# Capstone.net
KiCad netlist of a schematic drawn in Altium Designer
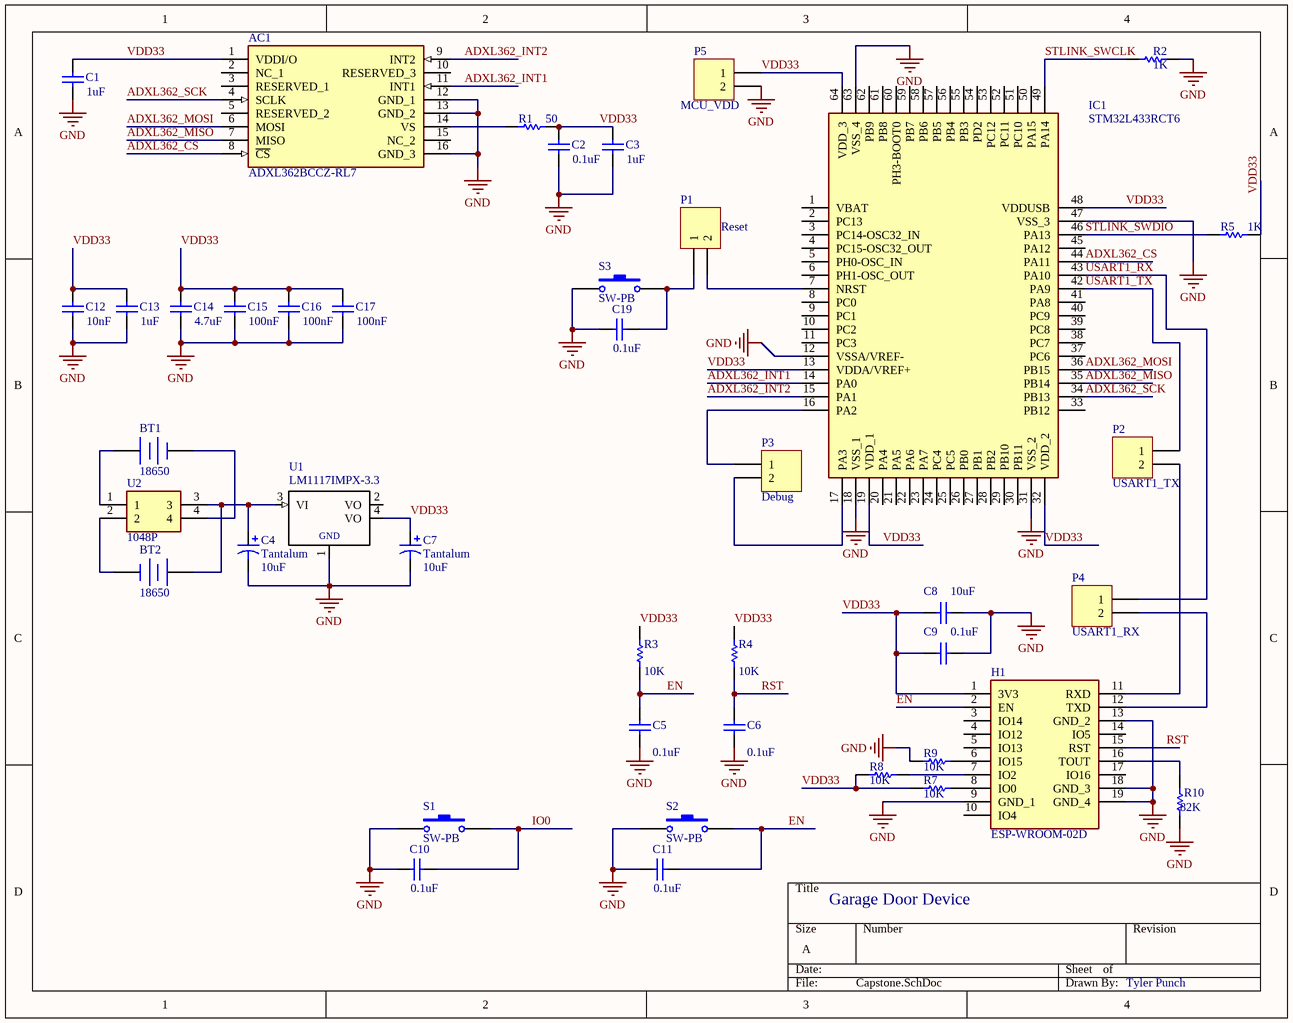
[diagram p0: Capstone.SchDoc]

(export (version "E")
  (design (tool "Eeschema 10.0.6"))
  (components
    (comp (ref "AC1")
      (value "ADXL362BCCZ-RL7")
      (footprint "SamacSys:CC-16-4")
      (description "Accelerometer")
      (fields (field (name "MOUSER PART NUMBER") "584-ADXL362BCCZ-R7"))
      (libsource (lib "*") (part "ADXL362BCCZ-RL7"))
    )
    (comp (ref "BT1")
      (value "18650")
      (footprint "BAT-2")
      (description "Multicell Battery")
      (fields (field (name "PUBLISHER") "Altium Limited"))
      (libsource (lib "Miscellaneous Devices") (part "Battery"))
    )
    (comp (ref "BT2")
      (value "18650")
      (footprint "BAT-2")
      (description "Multicell Battery")
      (fields (field (name "PUBLISHER") "Altium Limited"))
      (libsource (lib "Miscellaneous Devices") (part "Battery"))
    )
    (comp (ref "C1")
      (value "1uF")
      (footprint "*CAPC2012X88N")
      (description "Capacitor")
      (fields (field (name "Comment") "Cap") (field (name "PUBLISHER") "Altium Limited"))
      (libsource (lib "C0805C106K8PACTU") (part "Cap"))
    )
    (comp (ref "C2")
      (value "0.1uF")
      (footprint "*CAPC2012X88N")
      (description "Capacitor")
      (fields (field (name "Comment") "Cap") (field (name "PUBLISHER") "Altium Limited"))
      (libsource (lib "Miscellaneous Devices") (part "Cap"))
    )
    (comp (ref "C3")
      (value "1uF")
      (footprint "*CAPC2012X88N")
      (description "Capacitor")
      (fields (field (name "Comment") "Cap") (field (name "PUBLISHER") "Altium Limited"))
      (libsource (lib "Miscellaneous Devices") (part "Cap"))
    )
    (comp (ref "C4")
      (value "Tantalum")
      (footprint "RB7.6-15")
      (description "Polarized Capacitor (Radial)")
      (fields (field (name "ALTIUM_VALUE") "10uF") (field (name "PUBLISHER") "Altium Limited"))
      (libsource (lib "Miscellaneous Devices") (part "Cap Pol1"))
    )
    (comp (ref "C5")
      (value "0.1uF")
      (footprint "*CAPC2012X88N")
      (description "Capacitor")
      (fields (field (name "Comment") "Cap") (field (name "PUBLISHER") "Altium Limited"))
      (libsource (lib "Miscellaneous Devices") (part "Cap"))
    )
    (comp (ref "C6")
      (value "0.1uF")
      (footprint "*CAPC2012X88N")
      (description "Capacitor")
      (fields (field (name "Comment") "Cap") (field (name "PUBLISHER") "Altium Limited"))
      (libsource (lib "Miscellaneous Devices") (part "Cap"))
    )
    (comp (ref "C7")
      (value "Tantalum")
      (footprint "RB7.6-15")
      (description "Polarized Capacitor (Radial)")
      (fields (field (name "ALTIUM_VALUE") "10uF") (field (name "PUBLISHER") "Altium Limited"))
      (libsource (lib "Miscellaneous Devices") (part "Cap Pol1"))
    )
    (comp (ref "C8")
      (value "10uF")
      (footprint "*CAPC2012X88N")
      (description "Capacitor")
      (fields (field (name "Comment") "Cap") (field (name "PUBLISHER") "Altium Limited"))
      (libsource (lib "Miscellaneous Devices") (part "Cap"))
    )
    (comp (ref "C9")
      (value "0.1uF")
      (footprint "*CAPC2012X88N")
      (description "Capacitor")
      (fields (field (name "Comment") "Cap") (field (name "PUBLISHER") "Altium Limited"))
      (libsource (lib "Miscellaneous Devices") (part "Cap"))
    )
    (comp (ref "C10")
      (value "0.1uF")
      (footprint "*CAPC2012X88N")
      (description "Capacitor")
      (fields (field (name "Comment") "Cap") (field (name "PUBLISHER") "Altium Limited"))
      (libsource (lib "Miscellaneous Devices") (part "Cap"))
    )
    (comp (ref "C11")
      (value "0.1uF")
      (footprint "*CAPC2012X88N")
      (description "Capacitor")
      (fields (field (name "Comment") "Cap") (field (name "PUBLISHER") "Altium Limited"))
      (libsource (lib "Miscellaneous Devices") (part "Cap"))
    )
    (comp (ref "C12")
      (value "10nF")
      (footprint "*CAPC2012X88N")
      (description "Capacitor")
      (fields (field (name "Comment") "Cap") (field (name "PUBLISHER") "Altium Limited"))
      (libsource (lib "Miscellaneous Devices") (part "Cap"))
    )
    (comp (ref "C13")
      (value "1uF")
      (footprint "*CAPC2012X88N")
      (description "Capacitor")
      (fields (field (name "Comment") "Cap") (field (name "PUBLISHER") "Altium Limited"))
      (libsource (lib "Miscellaneous Devices") (part "Cap"))
    )
    (comp (ref "C14")
      (value "4.7uF")
      (footprint "*CAPC2012X88N")
      (description "Capacitor")
      (fields (field (name "Comment") "Cap") (field (name "PUBLISHER") "Altium Limited"))
      (libsource (lib "Miscellaneous Devices") (part "Cap"))
    )
    (comp (ref "C15")
      (value "100nF")
      (footprint "*CAPC2012X88N")
      (description "Capacitor")
      (fields (field (name "Comment") "Cap") (field (name "PUBLISHER") "Altium Limited"))
      (libsource (lib "Miscellaneous Devices") (part "Cap"))
    )
    (comp (ref "C16")
      (value "100nF")
      (footprint "*CAPC2012X88N")
      (description "Capacitor")
      (fields (field (name "Comment") "Cap") (field (name "PUBLISHER") "Altium Limited"))
      (libsource (lib "Miscellaneous Devices") (part "Cap"))
    )
    (comp (ref "C17")
      (value "100nF")
      (footprint "*CAPC2012X88N")
      (description "Capacitor")
      (fields (field (name "Comment") "Cap") (field (name "PUBLISHER") "Altium Limited"))
      (libsource (lib "Miscellaneous Devices") (part "Cap"))
    )
    (comp (ref "C19")
      (value "0.1uF")
      (footprint "RAD-0.3")
      (description "Capacitor")
      (fields (field (name "Comment") "Cap") (field (name "PUBLISHER") "Altium Limited"))
      (libsource (lib "Miscellaneous Devices") (part "Cap"))
    )
    (comp (ref "H1")
      (value "ESP-WROOM-02D")
      (footprint "SamacSys:ESPWROOM02D")
      (description "Hardware")
      (fields (field (name "MOUSER PART NUMBER") "356-ESPWROOM-02D"))
      (libsource (lib "*") (part "ESP-WROOM-02D"))
    )
    (comp (ref "IC1")
      (value "STM32L433RCT6")
      (footprint "SamacSys:QFP50P1200X1200X160-64N")
      (description "Integrated Circuit")
      (fields (field (name "MOUSER PART NUMBER") "511-STM32L433RCT6"))
      (libsource (lib "*") (part "STM32L433RCT6"))
    )
    (comp (ref "P1")
      (value "Reset")
      (footprint "HDR1X2")
      (description "Header, 2-Pin")
      (fields (field (name "PUBLISHER") "Altium Limited"))
      (libsource (lib "") (part "Header 2_2"))
    )
    (comp (ref "P2")
      (value "USART1_TX")
      (footprint "HDR1X2")
      (description "Header, 2-Pin")
      (fields (field (name "PUBLISHER") "Altium Limited"))
      (libsource (lib "") (part "Header 2_1"))
    )
    (comp (ref "P3")
      (value "Debug")
      (footprint "HDR1X2")
      (description "Header, 2-Pin")
      (fields (field (name "PUBLISHER") "Altium Limited"))
      (libsource (lib "Miscellaneous Connectors") (part "Header 2"))
    )
    (comp (ref "P4")
      (value "USART1_RX")
      (footprint "HDR1X2")
      (description "Header, 2-Pin")
      (fields (field (name "PUBLISHER") "Altium Limited"))
      (libsource (lib "") (part "Header 2_1"))
    )
    (comp (ref "P5")
      (value "MCU_VDD")
      (footprint "HDR1X2")
      (description "Header, 2-Pin")
      (fields (field (name "PUBLISHER") "Altium Limited"))
      (libsource (lib "") (part "Header 2_1"))
    )
    (comp (ref "R1")
      (value "50")
      (footprint "AXIAL-0.3")
      (description "Resistor")
      (fields (field (name "Comment") "Res1") (field (name "PUBLISHER") "Altium Limited"))
      (libsource (lib "Miscellaneous Devices") (part "Res1"))
    )
    (comp (ref "R2")
      (value "1K")
      (footprint "AXIAL-0.3")
      (description "Resistor")
      (fields (field (name "Comment") "Res1") (field (name "PUBLISHER") "Altium Limited"))
      (libsource (lib "Miscellaneous Devices") (part "Res1"))
    )
    (comp (ref "R3")
      (value "10K")
      (footprint "AXIAL-0.3")
      (description "Resistor")
      (fields (field (name "Comment") "Res1") (field (name "PUBLISHER") "Altium Limited"))
      (libsource (lib "Miscellaneous Devices") (part "Res1"))
    )
    (comp (ref "R4")
      (value "10K")
      (footprint "AXIAL-0.3")
      (description "Resistor")
      (fields (field (name "Comment") "Res1") (field (name "PUBLISHER") "Altium Limited"))
      (libsource (lib "Miscellaneous Devices") (part "Res1"))
    )
    (comp (ref "R5")
      (value "1K")
      (footprint "AXIAL-0.3")
      (description "Resistor")
      (fields (field (name "Comment") "Res1") (field (name "PUBLISHER") "Altium Limited"))
      (libsource (lib "Miscellaneous Devices") (part "Res1"))
    )
    (comp (ref "R7")
      (value "10K")
      (footprint "AXIAL-0.3")
      (description "Resistor")
      (fields (field (name "Comment") "Res1") (field (name "PUBLISHER") "Altium Limited"))
      (libsource (lib "Miscellaneous Devices") (part "Res1"))
    )
    (comp (ref "R8")
      (value "10K")
      (footprint "AXIAL-0.3")
      (description "Resistor")
      (fields (field (name "Comment") "Res1") (field (name "PUBLISHER") "Altium Limited"))
      (libsource (lib "Miscellaneous Devices") (part "Res1"))
    )
    (comp (ref "R9")
      (value "10K")
      (footprint "AXIAL-0.3")
      (description "Resistor")
      (fields (field (name "Comment") "Res1") (field (name "PUBLISHER") "Altium Limited"))
      (libsource (lib "Miscellaneous Devices") (part "Res1"))
    )
    (comp (ref "R10")
      (value "82K")
      (footprint "AXIAL-0.3")
      (description "Resistor")
      (fields (field (name "Comment") "Res1") (field (name "PUBLISHER") "Altium Limited"))
      (libsource (lib "Miscellaneous Devices") (part "Res1"))
    )
    (comp (ref "S1")
      (value "SW-PB")
      (footprint "SPST-2")
      (description "Switch")
      (fields (field (name "PUBLISHER") "Altium Limited"))
      (libsource (lib "Miscellaneous Devices") (part "SW-PB"))
    )
    (comp (ref "S2")
      (value "SW-PB")
      (footprint "SPST-2")
      (description "Switch")
      (fields (field (name "PUBLISHER") "Altium Limited"))
      (libsource (lib "Miscellaneous Devices") (part "SW-PB"))
    )
    (comp (ref "S3")
      (value "SW-PB")
      (footprint "SPST-2")
      (description "Switch")
      (fields (field (name "PUBLISHER") "Altium Limited"))
      (libsource (lib "Miscellaneous Devices") (part "SW-PB"))
    )
    (comp (ref "U1")
      (value "LM1117IMPX-3.3")
      (footprint "*SOT230P700X180-4N")
      (description "Linear Regulator, Fix, 3.3v, 800ma, Sot-223-4, Full Reel")
      (fields (field (name "MP") "LM1117MPX-3.3/NOPB") (field (name "MF") "Texas Instruments"))
      (libsource (lib "LM1117MPX-3.3") (part "LM1117MPX-3.3"))
    )
    (comp (ref "U2")
      (value "1048P")
      (footprint "SamacSys:1048P")
      (description "Undefined or Miscellaneous")
      (fields (field (name "MOUSER PART NUMBER") "534-1048P"))
      (libsource (lib "*") (part "1048P"))
    )
  )
  (nets
    (net (code "1") (name "/ADXL362_CS") (class "Default")
      (node (ref "AC1") (pin "8") (pinfunction "~{CS}_8") (pintype "input"))
      (node (ref "IC1") (pin "44") (pinfunction "PA11_44") (pintype "passive"))
    )
    (net (code "2") (name "/ADXL362_INT1") (class "Default")
      (node (ref "AC1") (pin "11") (pinfunction "INT1_11") (pintype "input"))
      (node (ref "IC1") (pin "14") (pinfunction "PA0_14") (pintype "passive"))
    )
    (net (code "3") (name "/ADXL362_INT2") (class "Default")
      (node (ref "AC1") (pin "9") (pinfunction "INT2_9") (pintype "input"))
      (node (ref "IC1") (pin "15") (pinfunction "PA1_15") (pintype "passive"))
    )
    (net (code "4") (name "/ADXL362_MISO") (class "Default")
      (node (ref "AC1") (pin "7") (pinfunction "MISO_7") (pintype "passive"))
      (node (ref "IC1") (pin "35") (pinfunction "PB14_35") (pintype "passive"))
    )
    (net (code "5") (name "/ADXL362_MOSI") (class "Default")
      (node (ref "AC1") (pin "6") (pinfunction "MOSI_6") (pintype "passive"))
      (node (ref "IC1") (pin "36") (pinfunction "PB15_36") (pintype "passive"))
    )
    (net (code "6") (name "/ADXL362_SCK") (class "Default")
      (node (ref "AC1") (pin "4") (pinfunction "SCLK_4") (pintype "input"))
      (node (ref "IC1") (pin "34") (pinfunction "PB13_34") (pintype "passive"))
    )
    (net (code "7") (name "/EN") (class "Default")
      (node (ref "C11") (pin "2") (pinfunction "2_2") (pintype "passive"))
      (node (ref "C5") (pin "1") (pinfunction "1_1") (pintype "passive"))
      (node (ref "H1") (pin "2") (pinfunction "EN_2") (pintype "passive"))
      (node (ref "R3") (pin "2") (pinfunction "2_2") (pintype "passive"))
      (node (ref "S2") (pin "2") (pinfunction "2_2") (pintype "passive"))
    )
    (net (code "8") (name "/IO0") (class "Default")
      (node (ref "C10") (pin "2") (pinfunction "2_2") (pintype "passive"))
      (node (ref "S1") (pin "2") (pinfunction "2_2") (pintype "passive"))
    )
    (net (code "9") (name "/RST") (class "Default")
      (node (ref "C6") (pin "1") (pinfunction "1_1") (pintype "passive"))
      (node (ref "H1") (pin "15") (pinfunction "RST_15") (pintype "passive"))
      (node (ref "R4") (pin "2") (pinfunction "2_2") (pintype "passive"))
    )
    (net (code "10") (name "/STLINK_SWCLK") (class "Default")
      (node (ref "IC1") (pin "49") (pinfunction "PA14_49") (pintype "passive"))
      (node (ref "R2") (pin "1") (pinfunction "1_1") (pintype "passive"))
    )
    (net (code "11") (name "/STLINK_SWDIO") (class "Default")
      (node (ref "IC1") (pin "46") (pinfunction "PA13_46") (pintype "passive"))
      (node (ref "R5") (pin "1") (pinfunction "1_1") (pintype "passive"))
    )
    (net (code "12") (name "/USART1_RX") (class "Default")
      (node (ref "IC1") (pin "43") (pinfunction "PA10_43") (pintype "passive"))
      (node (ref "P4") (pin "1") (pinfunction "1_1") (pintype "passive"))
    )
    (net (code "13") (name "/USART1_TX") (class "Default")
      (node (ref "IC1") (pin "42") (pinfunction "PA9_42") (pintype "passive"))
      (node (ref "P2") (pin "1") (pinfunction "1_1") (pintype "passive"))
    )
    (net (code "14") (name "/VDD33") (class "Default")
      (node (ref "AC1") (pin "1") (pinfunction "VDDI/O_1") (pintype "power_in"))
      (node (ref "C1") (pin "1") (pinfunction "1_1") (pintype "passive"))
      (node (ref "C12") (pin "2") (pinfunction "2_2") (pintype "passive"))
      (node (ref "C13") (pin "2") (pinfunction "2_2") (pintype "passive"))
      (node (ref "C14") (pin "2") (pinfunction "2_2") (pintype "passive"))
      (node (ref "C15") (pin "2") (pinfunction "2_2") (pintype "passive"))
      (node (ref "C16") (pin "2") (pinfunction "2_2") (pintype "passive"))
      (node (ref "C17") (pin "2") (pinfunction "2_2") (pintype "passive"))
      (node (ref "C2") (pin "2") (pinfunction "2_2") (pintype "passive"))
      (node (ref "C3") (pin "1") (pinfunction "1_1") (pintype "passive"))
      (node (ref "C7") (pin "1") (pinfunction "1_1") (pintype "passive"))
      (node (ref "C8") (pin "1") (pinfunction "1_1") (pintype "passive"))
      (node (ref "C9") (pin "1") (pinfunction "1_1") (pintype "passive"))
      (node (ref "H1") (pin "1") (pinfunction "3V3_1") (pintype "passive"))
      (node (ref "IC1") (pin "13") (pinfunction "VDDA/VREF+_13") (pintype "passive"))
      (node (ref "IC1") (pin "19") (pinfunction "VDD_1_19") (pintype "passive"))
      (node (ref "IC1") (pin "32") (pinfunction "VDD_2_32") (pintype "passive"))
      (node (ref "IC1") (pin "48") (pinfunction "VDDUSB_48") (pintype "passive"))
      (node (ref "IC1") (pin "64") (pinfunction "VDD_3_64") (pintype "passive"))
      (node (ref "P5") (pin "1") (pinfunction "1_1") (pintype "passive"))
      (node (ref "R1") (pin "2") (pinfunction "2_2") (pintype "passive"))
      (node (ref "R3") (pin "1") (pinfunction "1_1") (pintype "passive"))
      (node (ref "R4") (pin "1") (pinfunction "1_1") (pintype "passive"))
      (node (ref "R5") (pin "2") (pinfunction "2_2") (pintype "passive"))
      (node (ref "R7") (pin "1") (pinfunction "1_1") (pintype "passive"))
      (node (ref "R8") (pin "1") (pinfunction "1_1") (pintype "passive"))
      (node (ref "U1") (pin "4") (pinfunction "VO_4") (pintype "passive"))
    )
    (net (code "15") (name "GND") (class "Default")
      (node (ref "AC1") (pin "12") (pinfunction "GND_1_12") (pintype "power_in"))
      (node (ref "AC1") (pin "13") (pinfunction "GND_2_13") (pintype "power_in"))
      (node (ref "AC1") (pin "16") (pinfunction "GND_3_16") (pintype "power_in"))
      (node (ref "C1") (pin "2") (pinfunction "2_2") (pintype "passive"))
      (node (ref "C10") (pin "1") (pinfunction "1_1") (pintype "passive"))
      (node (ref "C11") (pin "1") (pinfunction "1_1") (pintype "passive"))
      (node (ref "C12") (pin "1") (pinfunction "1_1") (pintype "passive"))
      (node (ref "C13") (pin "1") (pinfunction "1_1") (pintype "passive"))
      (node (ref "C14") (pin "1") (pinfunction "1_1") (pintype "passive"))
      (node (ref "C15") (pin "1") (pinfunction "1_1") (pintype "passive"))
      (node (ref "C16") (pin "1") (pinfunction "1_1") (pintype "passive"))
      (node (ref "C17") (pin "1") (pinfunction "1_1") (pintype "passive"))
      (node (ref "C19") (pin "1") (pinfunction "1_1") (pintype "passive"))
      (node (ref "C2") (pin "1") (pinfunction "1_1") (pintype "passive"))
      (node (ref "C3") (pin "2") (pinfunction "2_2") (pintype "passive"))
      (node (ref "C4") (pin "2") (pinfunction "2_2") (pintype "passive"))
      (node (ref "C5") (pin "2") (pinfunction "2_2") (pintype "passive"))
      (node (ref "C6") (pin "2") (pinfunction "2_2") (pintype "passive"))
      (node (ref "C7") (pin "2") (pinfunction "2_2") (pintype "passive"))
      (node (ref "C8") (pin "2") (pinfunction "2_2") (pintype "passive"))
      (node (ref "C9") (pin "2") (pinfunction "2_2") (pintype "passive"))
      (node (ref "H1") (pin "13") (pinfunction "GND_2_13") (pintype "passive"))
      (node (ref "H1") (pin "18") (pinfunction "GND_3_18") (pintype "passive"))
      (node (ref "H1") (pin "19") (pinfunction "GND_4_19") (pintype "passive"))
      (node (ref "H1") (pin "9") (pinfunction "GND_1_9") (pintype "passive"))
      (node (ref "IC1") (pin "12") (pinfunction "VSSA/VREF-_12") (pintype "passive"))
      (node (ref "IC1") (pin "18") (pinfunction "VSS_1_18") (pintype "passive"))
      (node (ref "IC1") (pin "31") (pinfunction "VSS_2_31") (pintype "passive"))
      (node (ref "IC1") (pin "47") (pinfunction "VSS_3_47") (pintype "passive"))
      (node (ref "IC1") (pin "63") (pinfunction "VSS_4_63") (pintype "passive"))
      (node (ref "P5") (pin "2") (pinfunction "2_2") (pintype "passive"))
      (node (ref "R10") (pin "1") (pinfunction "1_1") (pintype "passive"))
      (node (ref "R2") (pin "2") (pinfunction "2_2") (pintype "passive"))
      (node (ref "R9") (pin "1") (pinfunction "1_1") (pintype "passive"))
      (node (ref "S1") (pin "1") (pinfunction "1_1") (pintype "passive"))
      (node (ref "S2") (pin "1") (pinfunction "1_1") (pintype "passive"))
      (node (ref "S3") (pin "1") (pinfunction "1_1") (pintype "passive"))
      (node (ref "U1") (pin "1") (pinfunction "GND_1") (pintype "passive"))
    )
    (net (code "16") (name "Net-(AC1-VS)") (class "Default")
      (node (ref "AC1") (pin "14") (pinfunction "VS_14") (pintype "passive"))
      (node (ref "R1") (pin "1") (pinfunction "1_1") (pintype "passive"))
    )
    (net (code "17") (name "Net-(BT1-+)") (class "Default")
      (node (ref "BT1") (pin "1") (pinfunction "+_1") (pintype "passive"))
      (node (ref "U2") (pin "1") (pinfunction "1_1") (pintype "passive"))
    )
    (net (code "18") (name "Net-(BT1--)") (class "Default")
      (node (ref "BT1") (pin "2") (pinfunction "-_2") (pintype "passive"))
      (node (ref "U2") (pin "4") (pinfunction "4_4") (pintype "passive"))
    )
    (net (code "19") (name "Net-(BT2-+)") (class "Default")
      (node (ref "BT2") (pin "1") (pinfunction "+_1") (pintype "passive"))
      (node (ref "C4") (pin "1") (pinfunction "1_1") (pintype "passive"))
      (node (ref "U1") (pin "3") (pinfunction "VI_3") (pintype "input"))
      (node (ref "U2") (pin "3") (pinfunction "3_3") (pintype "passive"))
    )
    (net (code "20") (name "Net-(BT2--)") (class "Default")
      (node (ref "BT2") (pin "2") (pinfunction "-_2") (pintype "passive"))
      (node (ref "U2") (pin "2") (pinfunction "2_2") (pintype "passive"))
    )
    (net (code "21") (name "Net-(C19-Pad2)") (class "Default")
      (node (ref "C19") (pin "2") (pinfunction "2_2") (pintype "passive"))
      (node (ref "P1") (pin "1") (pinfunction "1_1") (pintype "passive"))
      (node (ref "S3") (pin "2") (pinfunction "2_2") (pintype "passive"))
    )
    (net (code "22") (name "Net-(H1-IO0)") (class "Default")
      (node (ref "H1") (pin "8") (pinfunction "IO0_8") (pintype "passive"))
      (node (ref "R7") (pin "2") (pinfunction "2_2") (pintype "passive"))
    )
    (net (code "23") (name "Net-(H1-IO2)") (class "Default")
      (node (ref "H1") (pin "7") (pinfunction "IO2_7") (pintype "passive"))
      (node (ref "R8") (pin "2") (pinfunction "2_2") (pintype "passive"))
    )
    (net (code "24") (name "Net-(H1-IO15)") (class "Default")
      (node (ref "H1") (pin "6") (pinfunction "IO15_6") (pintype "passive"))
      (node (ref "R9") (pin "2") (pinfunction "2_2") (pintype "passive"))
    )
    (net (code "25") (name "Net-(H1-RXD)") (class "Default")
      (node (ref "H1") (pin "11") (pinfunction "RXD_11") (pintype "passive"))
      (node (ref "P2") (pin "2") (pinfunction "2_2") (pintype "passive"))
    )
    (net (code "26") (name "Net-(H1-TOUT)") (class "Default")
      (node (ref "H1") (pin "16") (pinfunction "TOUT_16") (pintype "passive"))
      (node (ref "R10") (pin "2") (pinfunction "2_2") (pintype "passive"))
    )
    (net (code "27") (name "Net-(H1-TXD)") (class "Default")
      (node (ref "H1") (pin "12") (pinfunction "TXD_12") (pintype "passive"))
      (node (ref "P4") (pin "2") (pinfunction "2_2") (pintype "passive"))
    )
    (net (code "28") (name "Net-(IC1-NRST)") (class "Default")
      (node (ref "IC1") (pin "7") (pinfunction "NRST_7") (pintype "passive"))
      (node (ref "P1") (pin "2") (pinfunction "2_2") (pintype "passive"))
    )
    (net (code "29") (name "Net-(IC1-PA2)") (class "Default")
      (node (ref "IC1") (pin "16") (pinfunction "PA2_16") (pintype "passive"))
      (node (ref "P3") (pin "1") (pinfunction "1_1") (pintype "passive"))
    )
    (net (code "30") (name "Net-(IC1-PA3)") (class "Default")
      (node (ref "IC1") (pin "17") (pinfunction "PA3_17") (pintype "passive"))
      (node (ref "P3") (pin "2") (pinfunction "2_2") (pintype "passive"))
    )
    (net (code "31") (name "unconnected-(AC1-NC_1-Pad2)") (class "Default")
      (node (ref "AC1") (pin "2") (pinfunction "NC_1_2") (pintype "passive"))
    )
    (net (code "32") (name "unconnected-(AC1-NC_2-Pad15)") (class "Default")
      (node (ref "AC1") (pin "15") (pinfunction "NC_2_15") (pintype "passive"))
    )
    (net (code "33") (name "unconnected-(AC1-RESERVED_1-Pad3)") (class "Default")
      (node (ref "AC1") (pin "3") (pinfunction "RESERVED_1_3") (pintype "passive"))
    )
    (net (code "34") (name "unconnected-(AC1-RESERVED_2-Pad5)") (class "Default")
      (node (ref "AC1") (pin "5") (pinfunction "RESERVED_2_5") (pintype "passive"))
    )
    (net (code "35") (name "unconnected-(AC1-RESERVED_3-Pad10)") (class "Default")
      (node (ref "AC1") (pin "10") (pinfunction "RESERVED_3_10") (pintype "passive"))
    )
    (net (code "36") (name "unconnected-(H1-IO4-Pad10)") (class "Default")
      (node (ref "H1") (pin "10") (pinfunction "IO4_10") (pintype "passive"))
    )
    (net (code "37") (name "unconnected-(H1-IO5-Pad14)") (class "Default")
      (node (ref "H1") (pin "14") (pinfunction "IO5_14") (pintype "passive"))
    )
    (net (code "38") (name "unconnected-(H1-IO12-Pad4)") (class "Default")
      (node (ref "H1") (pin "4") (pinfunction "IO12_4") (pintype "passive"))
    )
    (net (code "39") (name "unconnected-(H1-IO13-Pad5)") (class "Default")
      (node (ref "H1") (pin "5") (pinfunction "IO13_5") (pintype "passive"))
    )
    (net (code "40") (name "unconnected-(H1-IO14-Pad3)") (class "Default")
      (node (ref "H1") (pin "3") (pinfunction "IO14_3") (pintype "passive"))
    )
    (net (code "41") (name "unconnected-(H1-IO16-Pad17)") (class "Default")
      (node (ref "H1") (pin "17") (pinfunction "IO16_17") (pintype "passive"))
    )
    (net (code "42") (name "unconnected-(IC1-PA4-Pad20)") (class "Default")
      (node (ref "IC1") (pin "20") (pinfunction "PA4_20") (pintype "passive"))
    )
    (net (code "43") (name "unconnected-(IC1-PA5-Pad21)") (class "Default")
      (node (ref "IC1") (pin "21") (pinfunction "PA5_21") (pintype "passive"))
    )
    (net (code "44") (name "unconnected-(IC1-PA6-Pad22)") (class "Default")
      (node (ref "IC1") (pin "22") (pinfunction "PA6_22") (pintype "passive"))
    )
    (net (code "45") (name "unconnected-(IC1-PA7-Pad23)") (class "Default")
      (node (ref "IC1") (pin "23") (pinfunction "PA7_23") (pintype "passive"))
    )
    (net (code "46") (name "unconnected-(IC1-PA8-Pad41)") (class "Default")
      (node (ref "IC1") (pin "41") (pinfunction "PA8_41") (pintype "passive"))
    )
    (net (code "47") (name "unconnected-(IC1-PA12-Pad45)") (class "Default")
      (node (ref "IC1") (pin "45") (pinfunction "PA12_45") (pintype "passive"))
    )
    (net (code "48") (name "unconnected-(IC1-PA15-Pad50)") (class "Default")
      (node (ref "IC1") (pin "50") (pinfunction "PA15_50") (pintype "passive"))
    )
    (net (code "49") (name "unconnected-(IC1-PB0-Pad26)") (class "Default")
      (node (ref "IC1") (pin "26") (pinfunction "PB0_26") (pintype "passive"))
    )
    (net (code "50") (name "unconnected-(IC1-PB1-Pad27)") (class "Default")
      (node (ref "IC1") (pin "27") (pinfunction "PB1_27") (pintype "passive"))
    )
    (net (code "51") (name "unconnected-(IC1-PB2-Pad28)") (class "Default")
      (node (ref "IC1") (pin "28") (pinfunction "PB2_28") (pintype "passive"))
    )
    (net (code "52") (name "unconnected-(IC1-PB3-Pad55)") (class "Default")
      (node (ref "IC1") (pin "55") (pinfunction "PB3_55") (pintype "passive"))
    )
    (net (code "53") (name "unconnected-(IC1-PB4-Pad56)") (class "Default")
      (node (ref "IC1") (pin "56") (pinfunction "PB4_56") (pintype "passive"))
    )
    (net (code "54") (name "unconnected-(IC1-PB5-Pad57)") (class "Default")
      (node (ref "IC1") (pin "57") (pinfunction "PB5_57") (pintype "passive"))
    )
    (net (code "55") (name "unconnected-(IC1-PB6-Pad58)") (class "Default")
      (node (ref "IC1") (pin "58") (pinfunction "PB6_58") (pintype "passive"))
    )
    (net (code "56") (name "unconnected-(IC1-PB7-Pad59)") (class "Default")
      (node (ref "IC1") (pin "59") (pinfunction "PB7_59") (pintype "passive"))
    )
    (net (code "57") (name "unconnected-(IC1-PB8-Pad61)") (class "Default")
      (node (ref "IC1") (pin "61") (pinfunction "PB8_61") (pintype "passive"))
    )
    (net (code "58") (name "unconnected-(IC1-PB9-Pad62)") (class "Default")
      (node (ref "IC1") (pin "62") (pinfunction "PB9_62") (pintype "passive"))
    )
    (net (code "59") (name "unconnected-(IC1-PB10-Pad29)") (class "Default")
      (node (ref "IC1") (pin "29") (pinfunction "PB10_29") (pintype "passive"))
    )
    (net (code "60") (name "unconnected-(IC1-PB11-Pad30)") (class "Default")
      (node (ref "IC1") (pin "30") (pinfunction "PB11_30") (pintype "passive"))
    )
    (net (code "61") (name "unconnected-(IC1-PB12-Pad33)") (class "Default")
      (node (ref "IC1") (pin "33") (pinfunction "PB12_33") (pintype "passive"))
    )
    (net (code "62") (name "unconnected-(IC1-PC0-Pad8)") (class "Default")
      (node (ref "IC1") (pin "8") (pinfunction "PC0_8") (pintype "passive"))
    )
    (net (code "63") (name "unconnected-(IC1-PC1-Pad9)") (class "Default")
      (node (ref "IC1") (pin "9") (pinfunction "PC1_9") (pintype "passive"))
    )
    (net (code "64") (name "unconnected-(IC1-PC2-Pad10)") (class "Default")
      (node (ref "IC1") (pin "10") (pinfunction "PC2_10") (pintype "passive"))
    )
    (net (code "65") (name "unconnected-(IC1-PC3-Pad11)") (class "Default")
      (node (ref "IC1") (pin "11") (pinfunction "PC3_11") (pintype "passive"))
    )
    (net (code "66") (name "unconnected-(IC1-PC4-Pad24)") (class "Default")
      (node (ref "IC1") (pin "24") (pinfunction "PC4_24") (pintype "passive"))
    )
    (net (code "67") (name "unconnected-(IC1-PC5-Pad25)") (class "Default")
      (node (ref "IC1") (pin "25") (pinfunction "PC5_25") (pintype "passive"))
    )
    (net (code "68") (name "unconnected-(IC1-PC6-Pad37)") (class "Default")
      (node (ref "IC1") (pin "37") (pinfunction "PC6_37") (pintype "passive"))
    )
    (net (code "69") (name "unconnected-(IC1-PC7-Pad38)") (class "Default")
      (node (ref "IC1") (pin "38") (pinfunction "PC7_38") (pintype "passive"))
    )
    (net (code "70") (name "unconnected-(IC1-PC8-Pad39)") (class "Default")
      (node (ref "IC1") (pin "39") (pinfunction "PC8_39") (pintype "passive"))
    )
    (net (code "71") (name "unconnected-(IC1-PC9-Pad40)") (class "Default")
      (node (ref "IC1") (pin "40") (pinfunction "PC9_40") (pintype "passive"))
    )
    (net (code "72") (name "unconnected-(IC1-PC10-Pad51)") (class "Default")
      (node (ref "IC1") (pin "51") (pinfunction "PC10_51") (pintype "passive"))
    )
    (net (code "73") (name "unconnected-(IC1-PC11-Pad52)") (class "Default")
      (node (ref "IC1") (pin "52") (pinfunction "PC11_52") (pintype "passive"))
    )
    (net (code "74") (name "unconnected-(IC1-PC12-Pad53)") (class "Default")
      (node (ref "IC1") (pin "53") (pinfunction "PC12_53") (pintype "passive"))
    )
    (net (code "75") (name "unconnected-(IC1-PC13-Pad2)") (class "Default")
      (node (ref "IC1") (pin "2") (pinfunction "PC13_2") (pintype "passive"))
    )
    (net (code "76") (name "unconnected-(IC1-PC14-OSC32_IN-Pad3)") (class "Default")
      (node (ref "IC1") (pin "3") (pinfunction "PC14-OSC32_IN_3") (pintype "passive"))
    )
    (net (code "77") (name "unconnected-(IC1-PC15-OSC32_OUT-Pad4)") (class "Default")
      (node (ref "IC1") (pin "4") (pinfunction "PC15-OSC32_OUT_4") (pintype "passive"))
    )
    (net (code "78") (name "unconnected-(IC1-PD2-Pad54)") (class "Default")
      (node (ref "IC1") (pin "54") (pinfunction "PD2_54") (pintype "passive"))
    )
    (net (code "79") (name "unconnected-(IC1-PH0-OSC_IN-Pad5)") (class "Default")
      (node (ref "IC1") (pin "5") (pinfunction "PH0-OSC_IN_5") (pintype "passive"))
    )
    (net (code "80") (name "unconnected-(IC1-PH1-OSC_OUT-Pad6)") (class "Default")
      (node (ref "IC1") (pin "6") (pinfunction "PH1-OSC_OUT_6") (pintype "passive"))
    )
    (net (code "81") (name "unconnected-(IC1-PH3-BOOT0-Pad60)") (class "Default")
      (node (ref "IC1") (pin "60") (pinfunction "PH3-BOOT0_60") (pintype "passive"))
    )
    (net (code "82") (name "unconnected-(IC1-VBAT-Pad1)") (class "Default")
      (node (ref "IC1") (pin "1") (pinfunction "VBAT_1") (pintype "passive"))
    )
    (net (code "83") (name "unconnected-(U1-VO-Pad2)") (class "Default")
      (node (ref "U1") (pin "2") (pinfunction "VO_2") (pintype "passive"))
    )
  )
)
